# voltageRegulator.net
KiCad netlist of a schematic drawn in EAGLE
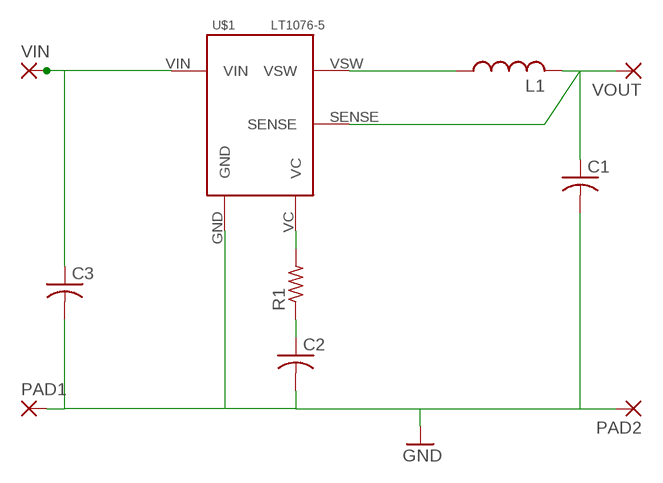
[diagram p0: schematic, sheet 1]

(export (version "E")
  (design (tool "Eeschema 10.0.6"))
  (components
    (comp (ref "C1")
      (value "C-US025-060X050")
      (footprint "eagle-import:C025-060X050")
      (libsource (lib "eagle-import") (part "C-US025-060X050"))
    )
    (comp (ref "C2")
      (value "C-US025-030X050")
      (footprint "eagle-import:C025-030X050")
      (libsource (lib "eagle-import") (part "C-US025-030X050"))
    )
    (comp (ref "C3")
      (value "C-US025-060X050")
      (footprint "eagle-import:C025-060X050")
      (libsource (lib "eagle-import") (part "C-US025-060X050"))
    )
    (comp (ref "L1")
      (value "L-US6000-XXX-RC")
      (footprint "eagle-import:6000-XXXX-RC")
      (libsource (lib "eagle-import") (part "L-US6000-XXX-RC"))
    )
    (comp (ref "PAD1")
      (value "3,81/1,4")
      (footprint "eagle-import:3,81_1,4")
      (libsource (lib "eagle-import") (part "3,81/1,4"))
    )
    (comp (ref "PAD2")
      (value "3,81/1,4")
      (footprint "eagle-import:3,81_1,4")
      (libsource (lib "eagle-import") (part "3,81/1,4"))
    )
    (comp (ref "R1")
      (value "R-US_0204/7")
      (footprint "eagle-import:0204_7")
      (libsource (lib "eagle-import") (part "R-US_0204/7"))
    )
    (comp (ref "U$1")
      (value "LT1076-5")
      (footprint "eagle-import:TO220-5")
      (libsource (lib "eagle-import") (part "LT1076-5"))
    )
    (comp (ref "VIN")
      (value "3,81/1,4")
      (footprint "eagle-import:3,81_1,4")
      (libsource (lib "eagle-import") (part "3,81/1,4"))
    )
    (comp (ref "VOUT")
      (value "3,81/1,4")
      (footprint "eagle-import:3,81_1,4")
      (libsource (lib "eagle-import") (part "3,81/1,4"))
    )
  )
  (nets
    (net (code "1") (name "GND") (class "Default")
      (node (ref "C1") (pin "2") (pinfunction "2_2") (pintype "passive"))
      (node (ref "C2") (pin "2") (pinfunction "2_2") (pintype "passive"))
      (node (ref "C3") (pin "2") (pinfunction "2_2") (pintype "passive"))
      (node (ref "PAD1") (pin "1") (pinfunction "P_1") (pintype "passive"))
      (node (ref "PAD2") (pin "1") (pinfunction "P_1") (pintype "passive"))
      (node (ref "U$1") (pin "GND") (pinfunction "GND_GND") (pintype "bidirectional"))
    )
    (net (code "2") (name "Net-(C2-Pad1)") (class "Default")
      (node (ref "C2") (pin "1") (pinfunction "1_1") (pintype "passive"))
      (node (ref "R1") (pin "1") (pinfunction "1_1") (pintype "passive"))
    )
    (net (code "3") (name "Net-(L1-Pad1)") (class "Default")
      (node (ref "L1") (pin "1") (pinfunction "1_1") (pintype "passive"))
      (node (ref "U$1") (pin "VSW") (pinfunction "VSW_VSW") (pintype "bidirectional"))
    )
    (net (code "4") (name "Net-(R1-Pad2)") (class "Default")
      (node (ref "R1") (pin "2") (pinfunction "2_2") (pintype "passive"))
      (node (ref "U$1") (pin "VC") (pinfunction "VC_VC") (pintype "bidirectional"))
    )
    (net (code "5") (name "Net-(VIN-P)") (class "Default")
      (node (ref "C3") (pin "1") (pinfunction "1_1") (pintype "passive"))
      (node (ref "U$1") (pin "VIN") (pinfunction "VIN_VIN") (pintype "bidirectional"))
      (node (ref "VIN") (pin "1") (pinfunction "P_1") (pintype "passive"))
    )
    (net (code "6") (name "Net-(VOUT-P)") (class "Default")
      (node (ref "C1") (pin "1") (pinfunction "1_1") (pintype "passive"))
      (node (ref "L1") (pin "2") (pinfunction "2_2") (pintype "passive"))
      (node (ref "U$1") (pin "SENSE") (pinfunction "SENSE_SENSE") (pintype "bidirectional"))
      (node (ref "VOUT") (pin "1") (pinfunction "P_1") (pintype "passive"))
    )
  )
)
